# DIO.net
KiCad netlist of a schematic drawn in Altium Designer
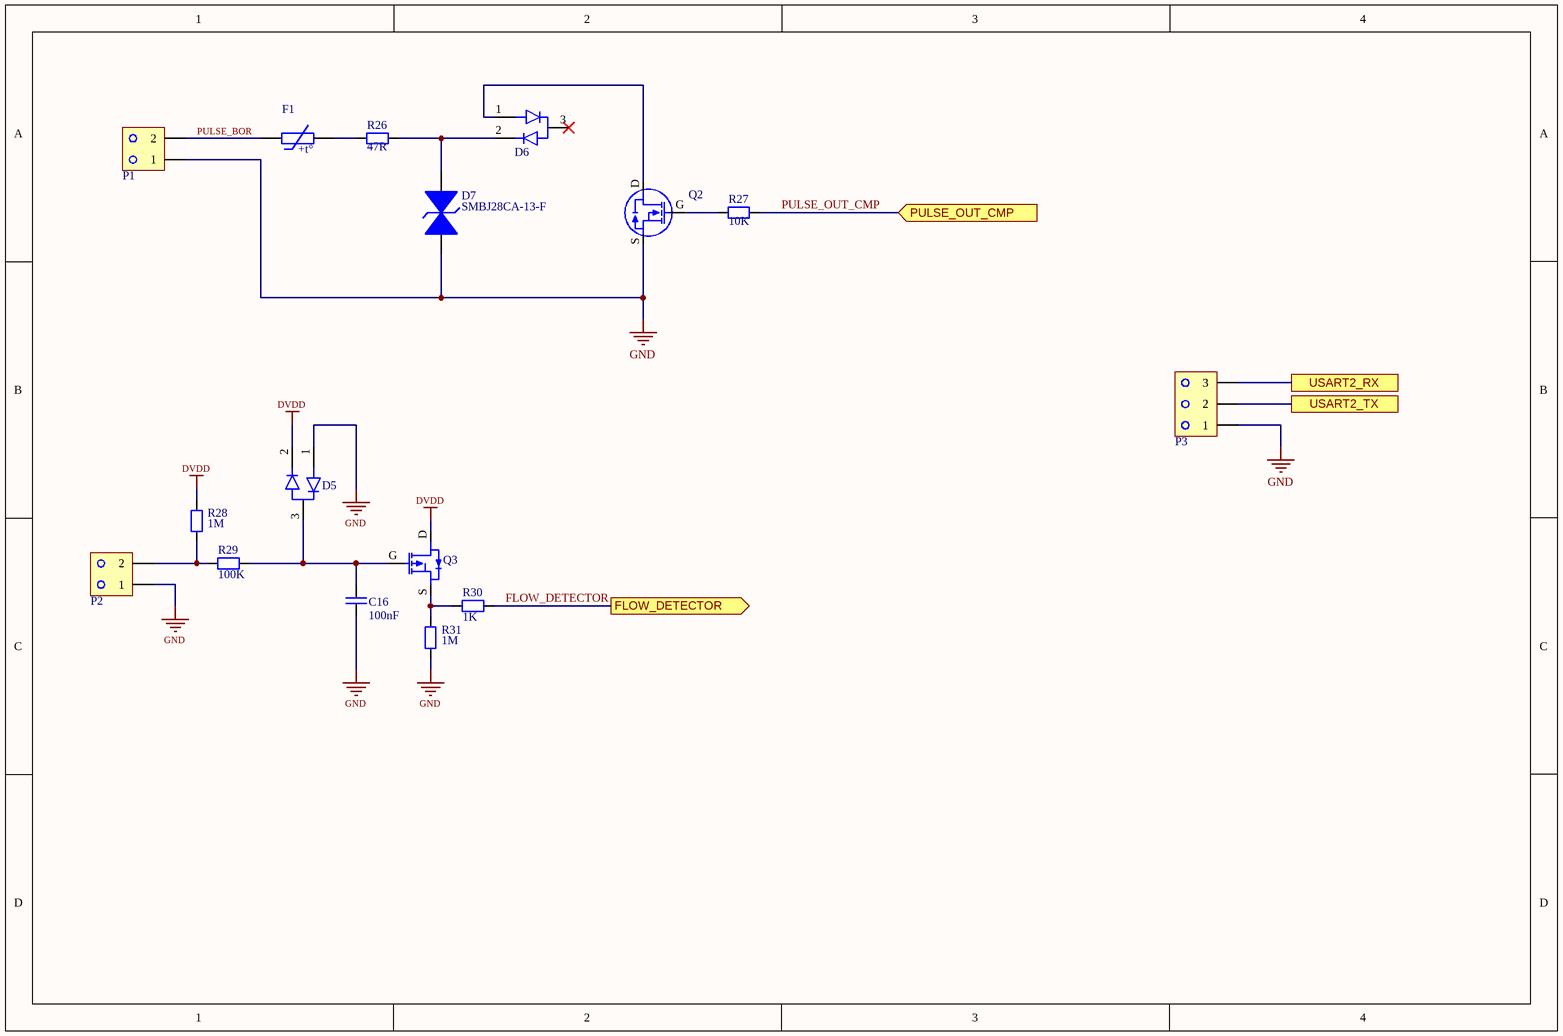
[diagram p0: DIO.SchDoc]

(export (version "E")
  (design (tool "Eeschema 10.0.6"))
  (components
    (comp (ref "C16")
      (value "100nF")
      (footprint "CAP_SM0805_YAGEOCC2_N")
      (description "CAP 100nF SM0805 X7R 25V YAGEO CC2")
      (fields
        (field (name "MANUFACTURER") "Yageo")
        (field (name "MANUFACTURER PART NUMBER") "CC0805KRX7R8BB104")
      )
      (libsource (lib "Yageo") (part "CC0805KRX7R8BB104"))
    )
    (comp (ref "D5")
      (value "BAV23S")
      (footprint "BAV23S")
      (description "DIODE ARRAY GP 250V 200MA SOT23")
      (fields (field (name "MANUFACTURER") "onsemi"))
      (libsource (lib "diode") (part "BAV23S"))
    )
    (comp (ref "D6")
      (value "BAV23S")
      (footprint "BAV23S")
      (description "DIODE ARRAY GP 250V 200MA SOT23")
      (fields (field (name "MANUFACTURER") "onsemi"))
      (libsource (lib "diode") (part "BAV23S"))
    )
    (comp (ref "D7")
      (value "SMBJ28CA-13-F")
      (footprint "SMBJ28CA-13-F")
      (fields
        (field (name "MANUFACTURER") "Diodes Incorporated")
        (field (name "MANUFACTURER PART NUMBER") "SMBJ24CA")
      )
      (libsource (lib "diode") (part "SMBJ28CA-13-F"))
    )
    (comp (ref "F1")
      (value "0ZCJ0005FF2E")
      (footprint "0ZCJ0005FF2E")
      (description "PTC RESET FUSE 60V 50MA 1206")
      (fields (field (name "MANUFACTURER") "Bel Fuse Inc."))
      (libsource (lib "fuse") (part "0ZCJ0005FF2E"))
    )
    (comp (ref "P1")
      (value "WJ15EDGVC-3.81-2P")
      (footprint "HEADER PLUG 2")
      (description "TERM BLOK FEMALE 1X2 3.81MM")
      (fields (field (name "MANUFACTURER") "Ningbo Kangnex Elec"))
      (libsource (lib "plug") (part "WJ15EDGVC-3.81-2P"))
    )
    (comp (ref "P2")
      (value "WJ15EDGVC-3.81-2P")
      (footprint "HEADER PLUG 2")
      (description "TERM BLOK FEMALE 1X2 3.81MM")
      (fields (field (name "MANUFACTURER") "Ningbo Kangnex Elec"))
      (libsource (lib "plug") (part "WJ15EDGVC-3.81-2P"))
    )
    (comp (ref "P3")
      (value "WJ15EDGVC-3.81-3P")
      (footprint "HEADER PLUG 3")
      (description "TERM BLOK FEMALE 1X3 3.81MM")
      (fields (field (name "MANUFACTURER") "Ningbo Kangnex Elec"))
      (libsource (lib "plug") (part "WJ15EDGVC-3.81-3P"))
    )
    (comp (ref "Q2")
      (value "DMG3402L-7")
      (footprint "DMG3402L-7")
      (description "N-CHANNEL ENHANCEMENT MODE FIELD EFFECT TRANSISTOR\r\n85mΩ @ VGS = 2.5V -> ID 2A\r\nV(BR)DDS 30V")
      (fields (field (name "MANUFACTURER") "Diodes Incorporated"))
      (libsource (lib "mosfet") (part "DMG3402L-7"))
    )
    (comp (ref "Q3")
      (value "DMG3401LSN-7")
      (footprint "DMG3401LSN-7")
      (description "P-CHANNEL ENHANCEMENT MODE MOSFET\r\nRDS(ON) = 85mΩ @ VGS = -2.5V -> ID -2.7A\r\nV(BR)DDS 30V")
      (fields (field (name "MANUFACTURER") "Diodes Incorporated"))
      (libsource (lib "mosfet") (part "DMG3401LSN-7"))
    )
    (comp (ref "R26")
      (value "47R")
      (footprint "RES_SM0805_YAGEORC_N")
      (description "RES 47R SM0805 YAGEO RC_L")
      (fields
        (field (name "MANUFACTURER") "Yageo")
        (field (name "MANUFACTURER PART NUMBER") "RC0805FR-0747RL")
      )
      (libsource (lib "Yageo") (part "RC0805FR-0747RL"))
    )
    (comp (ref "R27")
      (value "10K")
      (footprint "RES_SM0805_YAGEORC_N")
      (description "RES 10K SM0805 YAGEO RC_L")
      (fields
        (field (name "MANUFACTURER") "Yageo")
        (field (name "MANUFACTURER PART NUMBER") "RC0805FR-0710KL")
      )
      (libsource (lib "Yageo") (part "RC0805FR-0710KL"))
    )
    (comp (ref "R28")
      (value "1M")
      (footprint "RES_SM0805_YAGEORC_N")
      (description "RES 1M SM0805 YAGEO RC_L")
      (fields
        (field (name "MANUFACTURER") "Yageo")
        (field (name "MANUFACTURER PART NUMBER") "RC0805FR-071ML")
      )
      (libsource (lib "Yageo") (part "RC0805FR-071ML"))
    )
    (comp (ref "R29")
      (value "100K")
      (footprint "RES_SM0805_YAGEORC_N")
      (description "RES 100K SM0805 YAGEO RC_L")
      (fields
        (field (name "MANUFACTURER") "Yageo")
        (field (name "MANUFACTURER PART NUMBER") "RC0805FR-07100KL")
      )
      (libsource (lib "Yageo") (part "RC0805FR-07100KL"))
    )
    (comp (ref "R30")
      (value "1K")
      (footprint "RES_SM0805_YAGEORC_N")
      (description "RES 1K SM0805 YAGEO RC_L")
      (fields
        (field (name "MANUFACTURER") "Yageo")
        (field (name "MANUFACTURER PART NUMBER") "RC0805FR-071KL")
      )
      (libsource (lib "Yageo") (part "RC0805FR-071KL"))
    )
    (comp (ref "R31")
      (value "1M")
      (footprint "RES_SM0805_YAGEORC_N")
      (description "RES 1M SM0805 YAGEO RC_L")
      (fields
        (field (name "MANUFACTURER") "Yageo")
        (field (name "MANUFACTURER PART NUMBER") "RC0805FR-071ML")
      )
      (libsource (lib "Yageo") (part "RC0805FR-071ML"))
    )
  )
  (nets
    (net (code "1") (name "/FLOW_DETECTOR") (class "Default")
      (node (ref "R30") (pin "2") (pintype "passive"))
    )
    (net (code "2") (name "/PULSE_BOR") (class "Default")
      (node (ref "F1") (pin "1") (pinfunction "1_1") (pintype "passive"))
      (node (ref "P1") (pin "2") (pinfunction "2_2") (pintype "passive"))
    )
    (net (code "3") (name "/PULSE_OUT_CMP") (class "Default")
      (node (ref "R27") (pin "1") (pintype "passive"))
    )
    (net (code "4") (name "/USART2_RX") (class "Default")
      (node (ref "P3") (pin "3") (pinfunction "3_3") (pintype "passive"))
    )
    (net (code "5") (name "/USART2_TX") (class "Default")
      (node (ref "P3") (pin "2") (pinfunction "2_2") (pintype "passive"))
    )
    (net (code "6") (name "DVDD") (class "Default")
      (node (ref "D5") (pin "2") (pinfunction "2_2") (pintype "passive"))
      (node (ref "Q3") (pin "D") (pinfunction "D_D") (pintype "passive"))
      (node (ref "R28") (pin "2") (pintype "passive"))
    )
    (net (code "7") (name "GND") (class "Default")
      (node (ref "C16") (pin "2") (pintype "passive"))
      (node (ref "D5") (pin "1") (pinfunction "1_1") (pintype "passive"))
      (node (ref "D7") (pin "A") (pinfunction "A_A") (pintype "passive"))
      (node (ref "P1") (pin "1") (pinfunction "1_1") (pintype "passive"))
      (node (ref "P2") (pin "1") (pinfunction "1_1") (pintype "passive"))
      (node (ref "P3") (pin "1") (pinfunction "1_1") (pintype "passive"))
      (node (ref "Q2") (pin "S") (pinfunction "S_S") (pintype "passive"))
      (node (ref "R31") (pin "1") (pintype "passive"))
    )
    (net (code "8") (name "Net-(C16-Pad1)") (class "Default")
      (node (ref "C16") (pin "1") (pintype "passive"))
      (node (ref "D5") (pin "3") (pinfunction "3_3") (pintype "passive"))
      (node (ref "Q3") (pin "G") (pinfunction "G_G") (pintype "passive"))
      (node (ref "R29") (pin "2") (pintype "passive"))
    )
    (net (code "9") (name "Net-(D6-Pad1)") (class "Default")
      (node (ref "D6") (pin "1") (pinfunction "1_1") (pintype "passive"))
      (node (ref "Q2") (pin "D") (pinfunction "D_D") (pintype "passive"))
    )
    (net (code "10") (name "Net-(D6-Pad2)") (class "Default")
      (node (ref "D6") (pin "2") (pinfunction "2_2") (pintype "passive"))
      (node (ref "D7") (pin "K") (pinfunction "K_K") (pintype "passive"))
      (node (ref "R26") (pin "1") (pintype "passive"))
    )
    (net (code "11") (name "Net-(F1-Pad2)") (class "Default")
      (node (ref "F1") (pin "2") (pinfunction "2_2") (pintype "passive"))
      (node (ref "R26") (pin "2") (pintype "passive"))
    )
    (net (code "12") (name "Net-(P2-Pad2)") (class "Default")
      (node (ref "P2") (pin "2") (pinfunction "2_2") (pintype "passive"))
      (node (ref "R28") (pin "1") (pintype "passive"))
      (node (ref "R29") (pin "1") (pintype "passive"))
    )
    (net (code "13") (name "Net-(Q2-PadG)") (class "Default")
      (node (ref "Q2") (pin "G") (pinfunction "G_G") (pintype "passive"))
      (node (ref "R27") (pin "2") (pintype "passive"))
    )
    (net (code "14") (name "Net-(Q3-PadS)") (class "Default")
      (node (ref "Q3") (pin "S") (pinfunction "S_S") (pintype "passive"))
      (node (ref "R30") (pin "1") (pintype "passive"))
      (node (ref "R31") (pin "2") (pintype "passive"))
    )
    (net (code "15") (name "unconnected-(D6-Pad3)") (class "Default")
      (node (ref "D6") (pin "3") (pinfunction "3_3") (pintype "passive+no_connect"))
    )
  )
)
